# Temp_Sensor.net
KiCad netlist of a schematic drawn in Altium Designer
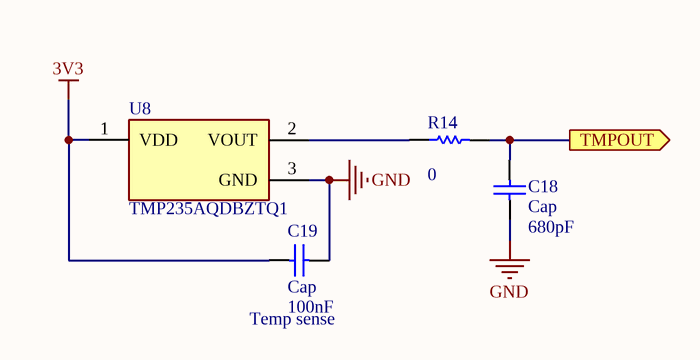
[diagram p0: Temp Sensor.SchDoc]

(export (version "E")
  (design (tool "Eeschema 10.0.6"))
  (components
    (comp (ref "C18")
      (value "Cap")
      (footprint "1608[0603]")
      (description "Capacitor")
      (fields (field (name "ALTIUM_VALUE") "680pF") (field (name "PUBLISHER") "Altium Limited"))
      (libsource (lib "Miscellaneous Devices") (part "Cap"))
    )
    (comp (ref "C19")
      (value "Cap")
      (footprint "1608[0603]")
      (description "Capacitor")
      (fields (field (name "ALTIUM_VALUE") "100nF") (field (name "PUBLISHER") "Altium Limited"))
      (libsource (lib "Miscellaneous Devices") (part "Cap"))
    )
    (comp (ref "R14")
      (value "0")
      (footprint "0402-A")
      (description "Resistor")
      (fields (field (name "Comment") "Res1") (field (name "PUBLISHER") "Altium Limited"))
      (libsource (lib "Miscellaneous Devices") (part "Res1"))
    )
    (comp (ref "U8")
      (value "TMP235AQDBZTQ1")
      (footprint "FP-DBZ0003A-MFG")
      (description "LOW-POWER HIGH-ACCURACY ANALOG O")
      (fields
        (field (name "MANUFACTURER") "Texas Instruments")
        (field (name "MANUFACTURER PART NUMBER") "TMP235A2DBZR")
      )
      (libsource (lib "Altium Content Vault") (part "1212246baba8f64ab0dd7b63bd818eb"))
    )
  )
  (nets
    (net (code "1") (name "/TMPOUT") (class "Default")
      (node (ref "C18") (pin "2") (pinfunction "2_2") (pintype "passive"))
      (node (ref "R14") (pin "2") (pinfunction "2_2") (pintype "passive"))
    )
    (net (code "2") (name "3V3") (class "Default")
      (node (ref "C19") (pin "2") (pinfunction "2_2") (pintype "passive"))
      (node (ref "U8") (pin "1") (pinfunction "VDD_1") (pintype "power_in"))
    )
    (net (code "3") (name "GND") (class "Default")
      (node (ref "C18") (pin "1") (pinfunction "1_1") (pintype "passive"))
      (node (ref "C19") (pin "1") (pinfunction "1_1") (pintype "passive"))
      (node (ref "U8") (pin "3") (pinfunction "GND_3") (pintype "power_in"))
    )
    (net (code "4") (name "Net-(U8-VOUT)") (class "Default")
      (node (ref "R14") (pin "1") (pinfunction "1_1") (pintype "passive"))
      (node (ref "U8") (pin "2") (pinfunction "VOUT_2") (pintype "passive"))
    )
  )
)
